# LinxBreakout.net
KiCad netlist of a schematic drawn in EAGLE
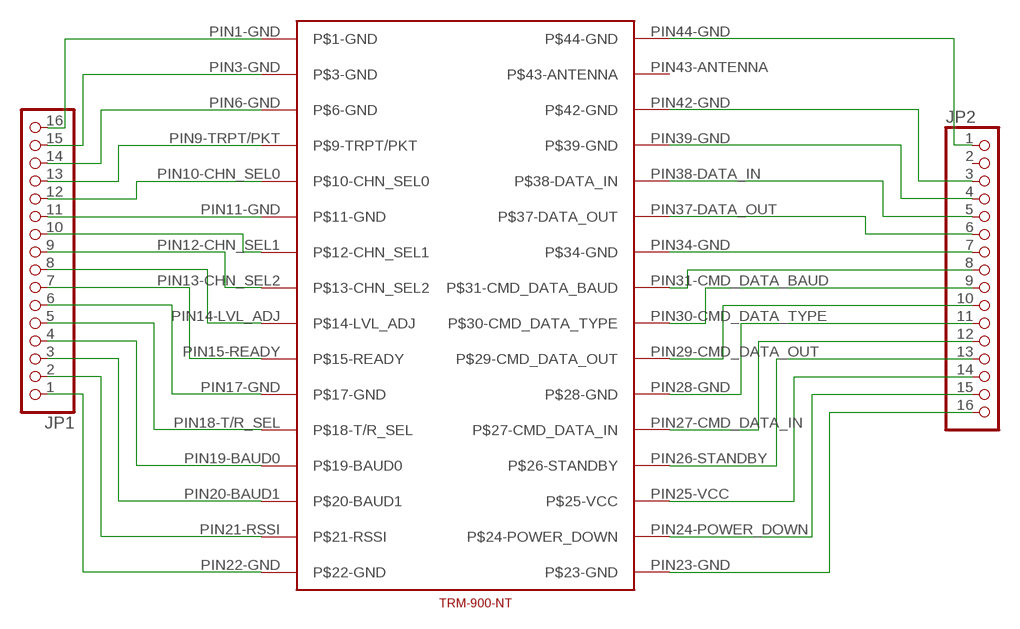
[diagram p0: schematic, sheet 1]

(export (version "E")
  (design (tool "Eeschema 10.0.6"))
  (components
    (comp (ref "JP1")
      (value "PINHD-1X16")
      (footprint "eagle-import:1X16")
      (libsource (lib "eagle-import") (part "PINHD-1X16"))
    )
    (comp (ref "JP2")
      (value "PINHD-1X16")
      (footprint "eagle-import:1X16")
      (libsource (lib "eagle-import") (part "PINHD-1X16"))
    )
    (comp (ref "U$1")
      (value "TRM-900-NT")
      (footprint "eagle-import:TRM-900-NT")
      (libsource (lib "eagle-import") (part "TRM-900-NT"))
    )
  )
  (nets
    (net (code "1") (name "Net-(U$1-P$1-GND)") (class "Default")
      (node (ref "JP1") (pin "16") (pinfunction "16_16") (pintype "passive"))
      (node (ref "U$1") (pin "PIN1-GND") (pinfunction "P$1-GND_PIN1-GND") (pintype "bidirectional"))
    )
    (net (code "2") (name "Net-(U$1-P$3-GND)") (class "Default")
      (node (ref "JP1") (pin "15") (pinfunction "15_15") (pintype "passive"))
      (node (ref "U$1") (pin "PIN3-GND") (pinfunction "P$3-GND_PIN3-GND") (pintype "bidirectional"))
    )
    (net (code "3") (name "Net-(U$1-P$6-GND)") (class "Default")
      (node (ref "JP1") (pin "14") (pinfunction "14_14") (pintype "passive"))
      (node (ref "U$1") (pin "PIN6-GND") (pinfunction "P$6-GND_PIN6-GND") (pintype "bidirectional"))
    )
    (net (code "4") (name "Net-(U$1-P$9-TRPT{slash}PKT)") (class "Default")
      (node (ref "JP1") (pin "13") (pinfunction "13_13") (pintype "passive"))
      (node (ref "U$1") (pin "PIN9-TRPT/PKT") (pinfunction "P$9-TRPT/PKT_PIN9-TRPT/PKT") (pintype "bidirectional"))
    )
    (net (code "5") (name "Net-(U$1-P$10-CHN_SEL0)") (class "Default")
      (node (ref "JP1") (pin "12") (pinfunction "12_12") (pintype "passive"))
      (node (ref "U$1") (pin "PIN10-CHN_SEL0") (pinfunction "P$10-CHN_SEL0_PIN10-CHN_SEL0") (pintype "bidirectional"))
    )
    (net (code "6") (name "Net-(U$1-P$11-GND)") (class "Default")
      (node (ref "JP1") (pin "11") (pinfunction "11_11") (pintype "passive"))
      (node (ref "U$1") (pin "PIN11-GND") (pinfunction "P$11-GND_PIN11-GND") (pintype "bidirectional"))
    )
    (net (code "7") (name "Net-(U$1-P$12-CHN_SEL1)") (class "Default")
      (node (ref "JP1") (pin "10") (pinfunction "10_10") (pintype "passive"))
      (node (ref "U$1") (pin "PIN12-CHN_SEL1") (pinfunction "P$12-CHN_SEL1_PIN12-CHN_SEL1") (pintype "bidirectional"))
    )
    (net (code "8") (name "Net-(U$1-P$13-CHN_SEL2)") (class "Default")
      (node (ref "JP1") (pin "9") (pinfunction "9_9") (pintype "passive"))
      (node (ref "U$1") (pin "PIN13-CHN_SEL2") (pinfunction "P$13-CHN_SEL2_PIN13-CHN_SEL2") (pintype "bidirectional"))
    )
    (net (code "9") (name "Net-(U$1-P$14-LVL_ADJ)") (class "Default")
      (node (ref "JP1") (pin "8") (pinfunction "8_8") (pintype "passive"))
      (node (ref "U$1") (pin "PIN14-LVL_ADJ") (pinfunction "P$14-LVL_ADJ_PIN14-LVL_ADJ") (pintype "bidirectional"))
    )
    (net (code "10") (name "Net-(U$1-P$15-READY)") (class "Default")
      (node (ref "JP1") (pin "7") (pinfunction "7_7") (pintype "passive"))
      (node (ref "U$1") (pin "PIN15-READY") (pinfunction "P$15-READY_PIN15-READY") (pintype "bidirectional"))
    )
    (net (code "11") (name "Net-(U$1-P$17-GND)") (class "Default")
      (node (ref "JP1") (pin "6") (pinfunction "6_6") (pintype "passive"))
      (node (ref "U$1") (pin "PIN17-GND") (pinfunction "P$17-GND_PIN17-GND") (pintype "bidirectional"))
    )
    (net (code "12") (name "Net-(U$1-P$18-T{slash}R_SEL)") (class "Default")
      (node (ref "JP1") (pin "5") (pinfunction "5_5") (pintype "passive"))
      (node (ref "U$1") (pin "PIN18-T/R_SEL") (pinfunction "P$18-T/R_SEL_PIN18-T/R_SEL") (pintype "bidirectional"))
    )
    (net (code "13") (name "Net-(U$1-P$19-BAUD0)") (class "Default")
      (node (ref "JP1") (pin "4") (pinfunction "4_4") (pintype "passive"))
      (node (ref "U$1") (pin "PIN19-BAUD0") (pinfunction "P$19-BAUD0_PIN19-BAUD0") (pintype "bidirectional"))
    )
    (net (code "14") (name "Net-(U$1-P$20-BAUD1)") (class "Default")
      (node (ref "JP1") (pin "3") (pinfunction "3_3") (pintype "passive"))
      (node (ref "U$1") (pin "PIN20-BAUD1") (pinfunction "P$20-BAUD1_PIN20-BAUD1") (pintype "bidirectional"))
    )
    (net (code "15") (name "Net-(U$1-P$21-RSSI)") (class "Default")
      (node (ref "JP1") (pin "2") (pinfunction "2_2") (pintype "passive"))
      (node (ref "U$1") (pin "PIN21-RSSI") (pinfunction "P$21-RSSI_PIN21-RSSI") (pintype "bidirectional"))
    )
    (net (code "16") (name "Net-(U$1-P$22-GND)") (class "Default")
      (node (ref "JP1") (pin "1") (pinfunction "1_1") (pintype "passive"))
      (node (ref "U$1") (pin "PIN22-GND") (pinfunction "P$22-GND_PIN22-GND") (pintype "bidirectional"))
    )
    (net (code "17") (name "Net-(U$1-P$23-GND)") (class "Default")
      (node (ref "JP2") (pin "16") (pinfunction "16_16") (pintype "passive"))
      (node (ref "U$1") (pin "PIN23-GND") (pinfunction "P$23-GND_PIN23-GND") (pintype "bidirectional"))
    )
    (net (code "18") (name "Net-(U$1-P$24-POWER_DOWN)") (class "Default")
      (node (ref "JP2") (pin "15") (pinfunction "15_15") (pintype "passive"))
      (node (ref "U$1") (pin "PIN24-POWER_DOWN") (pinfunction "P$24-POWER_DOWN_PIN24-POWER_DOWN") (pintype "bidirectional"))
    )
    (net (code "19") (name "Net-(U$1-P$25-VCC)") (class "Default")
      (node (ref "JP2") (pin "14") (pinfunction "14_14") (pintype "passive"))
      (node (ref "U$1") (pin "PIN25-VCC") (pinfunction "P$25-VCC_PIN25-VCC") (pintype "bidirectional"))
    )
    (net (code "20") (name "Net-(U$1-P$26-STANDBY)") (class "Default")
      (node (ref "JP2") (pin "13") (pinfunction "13_13") (pintype "passive"))
      (node (ref "U$1") (pin "PIN26-STANDBY") (pinfunction "P$26-STANDBY_PIN26-STANDBY") (pintype "bidirectional"))
    )
    (net (code "21") (name "Net-(U$1-P$27-CMD_DATA_IN)") (class "Default")
      (node (ref "JP2") (pin "12") (pinfunction "12_12") (pintype "passive"))
      (node (ref "U$1") (pin "PIN27-CMD_DATA_IN") (pinfunction "P$27-CMD_DATA_IN_PIN27-CMD_DATA_IN") (pintype "bidirectional"))
    )
    (net (code "22") (name "Net-(U$1-P$28-GND)") (class "Default")
      (node (ref "JP2") (pin "11") (pinfunction "11_11") (pintype "passive"))
      (node (ref "U$1") (pin "PIN28-GND") (pinfunction "P$28-GND_PIN28-GND") (pintype "bidirectional"))
    )
    (net (code "23") (name "Net-(U$1-P$29-CMD_DATA_OUT)") (class "Default")
      (node (ref "JP2") (pin "10") (pinfunction "10_10") (pintype "passive"))
      (node (ref "U$1") (pin "PIN29-CMD_DATA_OUT") (pinfunction "P$29-CMD_DATA_OUT_PIN29-CMD_DATA_OUT") (pintype "bidirectional"))
    )
    (net (code "24") (name "Net-(U$1-P$30-CMD_DATA_TYPE)") (class "Default")
      (node (ref "JP2") (pin "9") (pinfunction "9_9") (pintype "passive"))
      (node (ref "U$1") (pin "PIN30-CMD_DATA_TYPE") (pinfunction "P$30-CMD_DATA_TYPE_PIN30-CMD_DATA_TYPE") (pintype "bidirectional"))
    )
    (net (code "25") (name "Net-(U$1-P$31-CMD_DATA_BAUD)") (class "Default")
      (node (ref "JP2") (pin "8") (pinfunction "8_8") (pintype "passive"))
      (node (ref "U$1") (pin "PIN31-CMD_DATA_BAUD") (pinfunction "P$31-CMD_DATA_BAUD_PIN31-CMD_DATA_BAUD") (pintype "bidirectional"))
    )
    (net (code "26") (name "Net-(U$1-P$34-GND)") (class "Default")
      (node (ref "JP2") (pin "7") (pinfunction "7_7") (pintype "passive"))
      (node (ref "U$1") (pin "PIN34-GND") (pinfunction "P$34-GND_PIN34-GND") (pintype "bidirectional"))
    )
    (net (code "27") (name "Net-(U$1-P$37-DATA_OUT)") (class "Default")
      (node (ref "JP2") (pin "6") (pinfunction "6_6") (pintype "passive"))
      (node (ref "U$1") (pin "PIN37-DATA_OUT") (pinfunction "P$37-DATA_OUT_PIN37-DATA_OUT") (pintype "bidirectional"))
    )
    (net (code "28") (name "Net-(U$1-P$38-DATA_IN)") (class "Default")
      (node (ref "JP2") (pin "5") (pinfunction "5_5") (pintype "passive"))
      (node (ref "U$1") (pin "PIN38-DATA_IN") (pinfunction "P$38-DATA_IN_PIN38-DATA_IN") (pintype "bidirectional"))
    )
    (net (code "29") (name "Net-(U$1-P$39-GND)") (class "Default")
      (node (ref "JP2") (pin "4") (pinfunction "4_4") (pintype "passive"))
      (node (ref "U$1") (pin "PIN39-GND") (pinfunction "P$39-GND_PIN39-GND") (pintype "bidirectional"))
    )
    (net (code "30") (name "Net-(U$1-P$42-GND)") (class "Default")
      (node (ref "JP2") (pin "3") (pinfunction "3_3") (pintype "passive"))
      (node (ref "U$1") (pin "PIN42-GND") (pinfunction "P$42-GND_PIN42-GND") (pintype "bidirectional"))
    )
    (net (code "31") (name "Net-(U$1-P$44-GND)") (class "Default")
      (node (ref "JP2") (pin "1") (pinfunction "1_1") (pintype "passive"))
      (node (ref "U$1") (pin "PIN44-GND") (pinfunction "P$44-GND_PIN44-GND") (pintype "bidirectional"))
    )
    (net (code "32") (name "unconnected-(JP2-Pad2)") (class "Default")
      (node (ref "JP2") (pin "2") (pinfunction "2_2") (pintype "passive"))
    )
    (net (code "33") (name "unconnected-(U$1-P$43-ANTENNA-PadPIN43-ANTENNA)") (class "Default")
      (node (ref "U$1") (pin "PIN43-ANTENNA") (pinfunction "P$43-ANTENNA_PIN43-ANTENNA") (pintype "bidirectional"))
    )
  )
)
